# tempcontrol.net
KiCad netlist of a schematic drawn in EAGLE
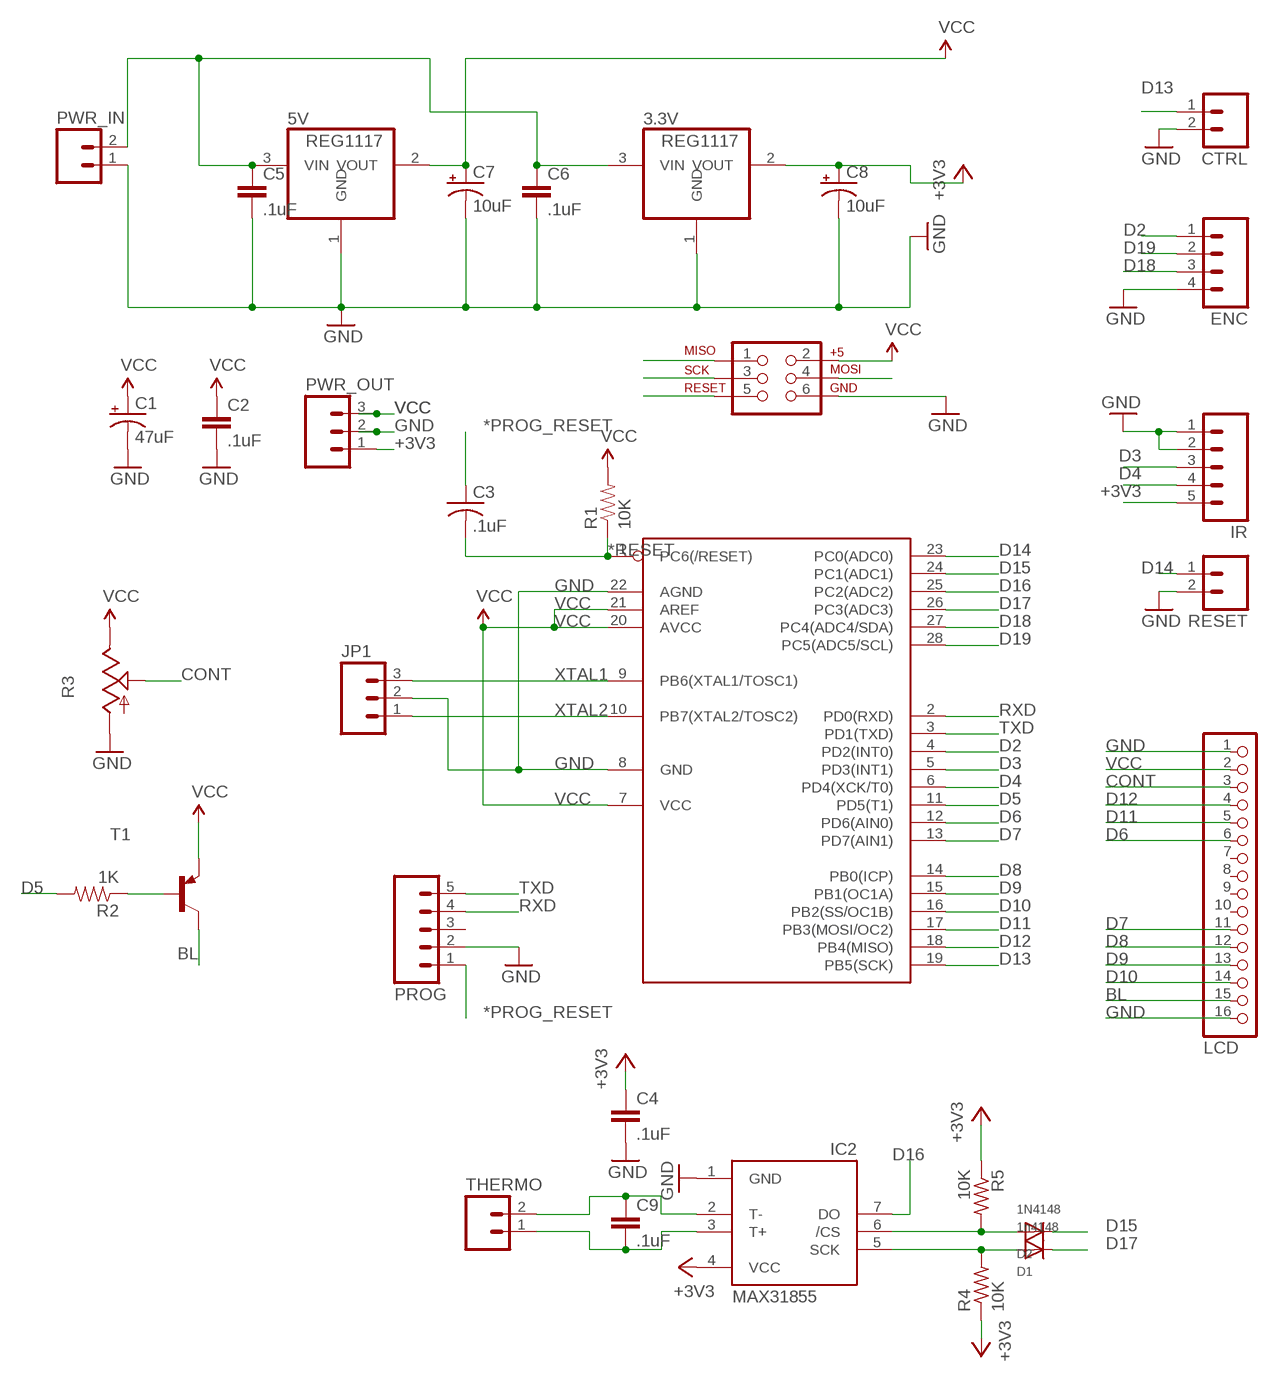
[diagram p0: schematic, sheet 1]

(export (version "E")
  (design (tool "Eeschema 10.0.6"))
  (components
    (comp (ref "3.3V")
      (value "REG1117")
      (footprint "eagle-import:SOT223")
      (libsource (lib "eagle-import") (part "REG1117"))
    )
    (comp (ref "5V")
      (value "REG1117")
      (footprint "eagle-import:SOT223")
      (libsource (lib "eagle-import") (part "REG1117"))
    )
    (comp (ref "C1")
      (value "47uF")
      (footprint "eagle-import:CPOL-RADIAL-10UF-25V")
      (libsource (lib "eagle-import") (part "CAP_POLPTH2"))
    )
    (comp (ref "C2")
      (value ".1uF")
      (footprint "eagle-import:0805")
      (libsource (lib "eagle-import") (part "CAP0805"))
    )
    (comp (ref "C3")
      (value ".1uF")
      (footprint "eagle-import:C0805")
      (libsource (lib "eagle-import") (part "C-USC0805"))
    )
    (comp (ref "C4")
      (value ".1uF")
      (footprint "eagle-import:0805")
      (libsource (lib "eagle-import") (part "CAP0805"))
    )
    (comp (ref "C5")
      (value ".1uF")
      (footprint "eagle-import:0805")
      (libsource (lib "eagle-import") (part "CAP0805"))
    )
    (comp (ref "C6")
      (value ".1uF")
      (footprint "eagle-import:0805")
      (libsource (lib "eagle-import") (part "CAP0805"))
    )
    (comp (ref "C7")
      (value "10uF")
      (footprint "eagle-import:EIA3528")
      (libsource (lib "eagle-import") (part "CAP_POL3528"))
    )
    (comp (ref "C8")
      (value "10uF")
      (footprint "eagle-import:EIA3528")
      (libsource (lib "eagle-import") (part "CAP_POL3528"))
    )
    (comp (ref "C9")
      (value ".1uF")
      (footprint "eagle-import:0805")
      (libsource (lib "eagle-import") (part "CAP0805"))
    )
    (comp (ref "CTRL")
      (value "M02LOCK")
      (footprint "eagle-import:1X02_LOCK")
      (libsource (lib "eagle-import") (part "M02LOCK"))
    )
    (comp (ref "D1")
      (value "1n4148")
      (footprint "eagle-import:SOD-323F")
      (libsource (lib "eagle-import") (part "DIODESOD-323F"))
    )
    (comp (ref "D2")
      (value "1N4148")
      (footprint "eagle-import:SOD-323F")
      (libsource (lib "eagle-import") (part "DIODESOD-323F"))
    )
    (comp (ref "ENC")
      (value "M04LOCK")
      (footprint "eagle-import:1X04_LOCK")
      (libsource (lib "eagle-import") (part "M04LOCK"))
    )
    (comp (ref "IC1")
      (value "MEGA8-P")
      (footprint "eagle-import:DIL28-3")
      (libsource (lib "eagle-import") (part "MEGA8-P"))
    )
    (comp (ref "IC2")
      (value "MAX31855")
      (footprint "eagle-import:SO08")
      (libsource (lib "eagle-import") (part "MAX6675"))
    )
    (comp (ref "IR")
      (value "M05LOCK")
      (footprint "eagle-import:1X05_LOCK")
      (libsource (lib "eagle-import") (part "M05LOCK"))
    )
    (comp (ref "JP1")
      (value "M03LOCK")
      (footprint "eagle-import:1X03_LOCK")
      (libsource (lib "eagle-import") (part "M03LOCK"))
    )
    (comp (ref "JP7")
      (value "LCD")
      (footprint "eagle-import:1X16")
      (libsource (lib "eagle-import") (part "PINHD-1X16"))
    )
    (comp (ref "PROG")
      (value "PROG")
      (footprint "eagle-import:1X05_LOCK")
      (libsource (lib "eagle-import") (part "M05LOCK"))
    )
    (comp (ref "PWR_IN")
      (value "M02LOCK")
      (footprint "eagle-import:1X02_LOCK")
      (libsource (lib "eagle-import") (part "M02LOCK"))
    )
    (comp (ref "PWR_OUT")
      (value "M03LOCK")
      (footprint "eagle-import:1X03_LOCK")
      (libsource (lib "eagle-import") (part "M03LOCK"))
    )
    (comp (ref "R1")
      (value "10K")
      (footprint "eagle-import:0805")
      (libsource (lib "eagle-import") (part "RESISTOR0805-RES"))
    )
    (comp (ref "R2")
      (value "1K")
      (footprint "eagle-import:0805")
      (libsource (lib "eagle-import") (part "RESISTOR0805-RES"))
    )
    (comp (ref "R3")
      (value "TRIM_US-B64Y")
      (footprint "eagle-import:B64Y")
      (libsource (lib "eagle-import") (part "TRIM_US-B64Y"))
    )
    (comp (ref "R4")
      (value "10K")
      (footprint "eagle-import:R0805")
      (libsource (lib "eagle-import") (part "R-US_R0805"))
    )
    (comp (ref "R5")
      (value "10K")
      (footprint "eagle-import:R0805")
      (libsource (lib "eagle-import") (part "R-US_R0805"))
    )
    (comp (ref "RESET")
      (value "M02LOCK")
      (footprint "eagle-import:1X02_LOCK")
      (libsource (lib "eagle-import") (part "M02LOCK"))
    )
    (comp (ref "T1")
      (value "2N3906-PNP-TO92-EBC")
      (footprint "eagle-import:TO92-EBC")
      (libsource (lib "eagle-import") (part "-PNP-TO92-EBC2N3906"))
    )
    (comp (ref "THERMO")
      (value "M02LOCK")
      (footprint "eagle-import:1X02_LOCK")
      (libsource (lib "eagle-import") (part "M02LOCK"))
    )
    (comp (ref "U$1")
      (value "AVR_SPI_PRG_6NS")
      (footprint "eagle-import:2X3-NS")
      (libsource (lib "eagle-import") (part "AVR_SPI_PRG_6NS"))
    )
  )
  (nets
    (net (code "1") (name "+3V3") (class "Default")
      (node (ref "3.3V") (pin "2") (pinfunction "VOUT_2") (pintype "power_in"))
      (node (ref "C4") (pin "1") (pinfunction "1_1") (pintype "passive"))
      (node (ref "C8") (pin "A") (pinfunction "+_A") (pintype "passive"))
      (node (ref "IC2") (pin "4") (pinfunction "VCC_4") (pintype "power_in"))
      (node (ref "IR") (pin "5") (pinfunction "5_5") (pintype "passive"))
      (node (ref "PWR_OUT") (pin "1") (pinfunction "1_1") (pintype "passive"))
      (node (ref "R4") (pin "1") (pinfunction "1_1") (pintype "passive"))
      (node (ref "R5") (pin "1") (pinfunction "1_1") (pintype "passive"))
    )
    (net (code "2") (name "/*PROG_RESET") (class "Default")
      (node (ref "C3") (pin "1") (pinfunction "1_1") (pintype "passive"))
      (node (ref "PROG") (pin "1") (pinfunction "1_1") (pintype "passive"))
    )
    (net (code "3") (name "/*RESET") (class "Default")
      (node (ref "C3") (pin "2") (pinfunction "2_2") (pintype "passive"))
      (node (ref "IC1") (pin "1") (pinfunction "PC6(/RESET)_1") (pintype "bidirectional"))
      (node (ref "R1") (pin "1") (pinfunction "1_1") (pintype "passive"))
      (node (ref "U$1") (pin "5") (pinfunction "5_5") (pintype "passive"))
    )
    (net (code "4") (name "/BL") (class "Default")
      (node (ref "JP7") (pin "15") (pinfunction "15_15") (pintype "passive"))
      (node (ref "T1") (pin "C") (pinfunction "C_C") (pintype "passive"))
    )
    (net (code "5") (name "/CONT") (class "Default")
      (node (ref "JP7") (pin "3") (pinfunction "3_3") (pintype "passive"))
      (node (ref "R3") (pin "S") (pinfunction "S_S") (pintype "passive"))
    )
    (net (code "6") (name "/D2") (class "Default")
      (node (ref "ENC") (pin "1") (pinfunction "1_1") (pintype "passive"))
      (node (ref "IC1") (pin "4") (pinfunction "PD2(INT0)_4") (pintype "bidirectional"))
    )
    (net (code "7") (name "/D3") (class "Default")
      (node (ref "IC1") (pin "5") (pinfunction "PD3(INT1)_5") (pintype "bidirectional"))
      (node (ref "IR") (pin "3") (pinfunction "3_3") (pintype "passive"))
    )
    (net (code "8") (name "/D4") (class "Default")
      (node (ref "IC1") (pin "6") (pinfunction "PD4(XCK/T0)_6") (pintype "bidirectional"))
      (node (ref "IR") (pin "4") (pinfunction "4_4") (pintype "passive"))
    )
    (net (code "9") (name "/D5") (class "Default")
      (node (ref "IC1") (pin "11") (pinfunction "PD5(T1)_11") (pintype "bidirectional"))
      (node (ref "R2") (pin "2") (pinfunction "2_2") (pintype "passive"))
    )
    (net (code "10") (name "/D6") (class "Default")
      (node (ref "IC1") (pin "12") (pinfunction "PD6(AIN0)_12") (pintype "bidirectional"))
      (node (ref "JP7") (pin "6") (pinfunction "6_6") (pintype "passive"))
    )
    (net (code "11") (name "/D7") (class "Default")
      (node (ref "IC1") (pin "13") (pinfunction "PD7(AIN1)_13") (pintype "bidirectional"))
      (node (ref "JP7") (pin "11") (pinfunction "11_11") (pintype "passive"))
    )
    (net (code "12") (name "/D8") (class "Default")
      (node (ref "IC1") (pin "14") (pinfunction "PB0(ICP)_14") (pintype "bidirectional"))
      (node (ref "JP7") (pin "12") (pinfunction "12_12") (pintype "passive"))
    )
    (net (code "13") (name "/D9") (class "Default")
      (node (ref "IC1") (pin "15") (pinfunction "PB1(OC1A)_15") (pintype "bidirectional"))
      (node (ref "JP7") (pin "13") (pinfunction "13_13") (pintype "passive"))
    )
    (net (code "14") (name "/D10") (class "Default")
      (node (ref "IC1") (pin "16") (pinfunction "PB2(SS/OC1B)_16") (pintype "bidirectional"))
      (node (ref "JP7") (pin "14") (pinfunction "14_14") (pintype "passive"))
    )
    (net (code "15") (name "/D11") (class "Default")
      (node (ref "IC1") (pin "17") (pinfunction "PB3(MOSI/OC2)_17") (pintype "bidirectional"))
      (node (ref "JP7") (pin "5") (pinfunction "5_5") (pintype "passive"))
      (node (ref "U$1") (pin "4") (pinfunction "4_4") (pintype "passive"))
    )
    (net (code "16") (name "/D12") (class "Default")
      (node (ref "IC1") (pin "18") (pinfunction "PB4(MISO)_18") (pintype "bidirectional"))
      (node (ref "JP7") (pin "4") (pinfunction "4_4") (pintype "passive"))
      (node (ref "U$1") (pin "1") (pinfunction "1_1") (pintype "passive"))
    )
    (net (code "17") (name "/D13") (class "Default")
      (node (ref "CTRL") (pin "1") (pinfunction "1_1") (pintype "passive"))
      (node (ref "IC1") (pin "19") (pinfunction "PB5(SCK)_19") (pintype "bidirectional"))
      (node (ref "U$1") (pin "3") (pinfunction "3_3") (pintype "passive"))
    )
    (net (code "18") (name "/D14") (class "Default")
      (node (ref "IC1") (pin "23") (pinfunction "PC0(ADC0)_23") (pintype "bidirectional"))
      (node (ref "RESET") (pin "1") (pinfunction "1_1") (pintype "passive"))
    )
    (net (code "19") (name "/D15") (class "Default")
      (node (ref "D2") (pin "C") (pinfunction "C_C") (pintype "passive"))
      (node (ref "IC1") (pin "24") (pinfunction "PC1(ADC1)_24") (pintype "bidirectional"))
    )
    (net (code "20") (name "/D16") (class "Default")
      (node (ref "IC1") (pin "25") (pinfunction "PC2(ADC2)_25") (pintype "bidirectional"))
      (node (ref "IC2") (pin "7") (pinfunction "DO_7") (pintype "output"))
    )
    (net (code "21") (name "/D17") (class "Default")
      (node (ref "D1") (pin "C") (pinfunction "C_C") (pintype "passive"))
      (node (ref "IC1") (pin "26") (pinfunction "PC3(ADC3)_26") (pintype "bidirectional"))
    )
    (net (code "22") (name "/D18") (class "Default")
      (node (ref "ENC") (pin "3") (pinfunction "3_3") (pintype "passive"))
      (node (ref "IC1") (pin "27") (pinfunction "PC4(ADC4/SDA)_27") (pintype "bidirectional"))
    )
    (net (code "23") (name "/D19") (class "Default")
      (node (ref "ENC") (pin "2") (pinfunction "2_2") (pintype "passive"))
      (node (ref "IC1") (pin "28") (pinfunction "PC5(ADC5/SCL)_28") (pintype "bidirectional"))
    )
    (net (code "24") (name "/RXD") (class "Default")
      (node (ref "IC1") (pin "2") (pinfunction "PD0(RXD)_2") (pintype "bidirectional"))
      (node (ref "PROG") (pin "4") (pinfunction "4_4") (pintype "passive"))
    )
    (net (code "25") (name "/TXD") (class "Default")
      (node (ref "IC1") (pin "3") (pinfunction "PD1(TXD)_3") (pintype "bidirectional"))
      (node (ref "PROG") (pin "5") (pinfunction "5_5") (pintype "passive"))
    )
    (net (code "26") (name "/XTAL1") (class "Default")
      (node (ref "IC1") (pin "9") (pinfunction "PB6(XTAL1/TOSC1)_9") (pintype "bidirectional"))
      (node (ref "JP1") (pin "3") (pinfunction "3_3") (pintype "passive"))
    )
    (net (code "27") (name "/XTAL2") (class "Default")
      (node (ref "IC1") (pin "10") (pinfunction "PB7(XTAL2/TOSC2)_10") (pintype "bidirectional"))
      (node (ref "JP1") (pin "1") (pinfunction "1_1") (pintype "passive"))
    )
    (net (code "28") (name "GND") (class "Default")
      (node (ref "3.3V") (pin "1") (pinfunction "GND_1") (pintype "power_in"))
      (node (ref "5V") (pin "1") (pinfunction "GND_1") (pintype "power_in"))
      (node (ref "C1") (pin "2") (pinfunction "-_2") (pintype "passive"))
      (node (ref "C2") (pin "2") (pinfunction "2_2") (pintype "passive"))
      (node (ref "C4") (pin "2") (pinfunction "2_2") (pintype "passive"))
      (node (ref "C5") (pin "2") (pinfunction "2_2") (pintype "passive"))
      (node (ref "C6") (pin "2") (pinfunction "2_2") (pintype "passive"))
      (node (ref "C7") (pin "C") (pinfunction "-_C") (pintype "passive"))
      (node (ref "C8") (pin "C") (pinfunction "-_C") (pintype "passive"))
      (node (ref "CTRL") (pin "2") (pinfunction "2_2") (pintype "passive"))
      (node (ref "ENC") (pin "4") (pinfunction "4_4") (pintype "passive"))
      (node (ref "IC1") (pin "22") (pinfunction "AGND_22") (pintype "bidirectional"))
      (node (ref "IC1") (pin "8") (pinfunction "GND_8") (pintype "bidirectional"))
      (node (ref "IC2") (pin "1") (pinfunction "GND_1") (pintype "power_in"))
      (node (ref "IR") (pin "1") (pinfunction "1_1") (pintype "passive"))
      (node (ref "IR") (pin "2") (pinfunction "2_2") (pintype "passive"))
      (node (ref "JP1") (pin "2") (pinfunction "2_2") (pintype "passive"))
      (node (ref "JP7") (pin "1") (pinfunction "1_1") (pintype "passive"))
      (node (ref "JP7") (pin "16") (pinfunction "16_16") (pintype "passive"))
      (node (ref "PROG") (pin "2") (pinfunction "2_2") (pintype "passive"))
      (node (ref "PWR_IN") (pin "1") (pinfunction "1_1") (pintype "passive"))
      (node (ref "PWR_OUT") (pin "2") (pinfunction "2_2") (pintype "passive"))
      (node (ref "R3") (pin "A") (pinfunction "A_A") (pintype "passive"))
      (node (ref "RESET") (pin "2") (pinfunction "2_2") (pintype "passive"))
      (node (ref "U$1") (pin "6") (pinfunction "6_6") (pintype "passive"))
    )
    (net (code "29") (name "Net-(3.3V-VIN)") (class "Default")
      (node (ref "3.3V") (pin "3") (pinfunction "VIN_3") (pintype "input"))
      (node (ref "5V") (pin "3") (pinfunction "VIN_3") (pintype "input"))
      (node (ref "C5") (pin "1") (pinfunction "1_1") (pintype "passive"))
      (node (ref "C6") (pin "1") (pinfunction "1_1") (pintype "passive"))
      (node (ref "PWR_IN") (pin "2") (pinfunction "2_2") (pintype "passive"))
    )
    (net (code "30") (name "Net-(IC2-SCK)") (class "Default")
      (node (ref "D1") (pin "A") (pinfunction "A_A") (pintype "passive"))
      (node (ref "IC2") (pin "5") (pinfunction "SCK_5") (pintype "input"))
      (node (ref "R4") (pin "2") (pinfunction "2_2") (pintype "passive"))
    )
    (net (code "31") (name "Net-(IC2-T+)") (class "Default")
      (node (ref "C9") (pin "2") (pinfunction "2_2") (pintype "passive"))
      (node (ref "IC2") (pin "3") (pinfunction "T+_3") (pintype "input"))
      (node (ref "THERMO") (pin "1") (pinfunction "1_1") (pintype "passive"))
    )
    (net (code "32") (name "Net-(IC2-T-)") (class "Default")
      (node (ref "C9") (pin "1") (pinfunction "1_1") (pintype "passive"))
      (node (ref "IC2") (pin "2") (pinfunction "T-_2") (pintype "input"))
      (node (ref "THERMO") (pin "2") (pinfunction "2_2") (pintype "passive"))
    )
    (net (code "33") (name "Net-(IC2-{slash}CS)") (class "Default")
      (node (ref "D2") (pin "A") (pinfunction "A_A") (pintype "passive"))
      (node (ref "IC2") (pin "6") (pinfunction "/CS_6") (pintype "input"))
      (node (ref "R5") (pin "2") (pinfunction "2_2") (pintype "passive"))
    )
    (net (code "34") (name "Net-(R2-Pad1)") (class "Default")
      (node (ref "R2") (pin "1") (pinfunction "1_1") (pintype "passive"))
      (node (ref "T1") (pin "B") (pinfunction "B_B") (pintype "passive"))
    )
    (net (code "35") (name "VCC") (class "Default")
      (node (ref "5V") (pin "2") (pinfunction "VOUT_2") (pintype "power_in"))
      (node (ref "C1") (pin "1") (pinfunction "+_1") (pintype "passive"))
      (node (ref "C2") (pin "1") (pinfunction "1_1") (pintype "passive"))
      (node (ref "C7") (pin "A") (pinfunction "+_A") (pintype "passive"))
      (node (ref "IC1") (pin "20") (pinfunction "AVCC_20") (pintype "bidirectional"))
      (node (ref "IC1") (pin "21") (pinfunction "AREF_21") (pintype "bidirectional"))
      (node (ref "IC1") (pin "7") (pinfunction "VCC_7") (pintype "bidirectional"))
      (node (ref "JP7") (pin "2") (pinfunction "2_2") (pintype "passive"))
      (node (ref "PWR_OUT") (pin "3") (pinfunction "3_3") (pintype "passive"))
      (node (ref "R1") (pin "2") (pinfunction "2_2") (pintype "passive"))
      (node (ref "R3") (pin "E") (pinfunction "E_E") (pintype "passive"))
      (node (ref "T1") (pin "E") (pinfunction "E_E") (pintype "passive"))
      (node (ref "U$1") (pin "2") (pinfunction "2_2") (pintype "passive"))
    )
    (net (code "36") (name "unconnected-(JP7-Pad7)") (class "Default")
      (node (ref "JP7") (pin "7") (pinfunction "7_7") (pintype "passive"))
    )
    (net (code "37") (name "unconnected-(JP7-Pad8)") (class "Default")
      (node (ref "JP7") (pin "8") (pinfunction "8_8") (pintype "passive"))
    )
    (net (code "38") (name "unconnected-(JP7-Pad9)") (class "Default")
      (node (ref "JP7") (pin "9") (pinfunction "9_9") (pintype "passive"))
    )
    (net (code "39") (name "unconnected-(JP7-Pad10)") (class "Default")
      (node (ref "JP7") (pin "10") (pinfunction "10_10") (pintype "passive"))
    )
    (net (code "40") (name "unconnected-(PROG-Pad3)") (class "Default")
      (node (ref "PROG") (pin "3") (pinfunction "3_3") (pintype "passive"))
    )
  )
)
